# ADE9000.net
KiCad netlist of a schematic drawn in Altium Designer
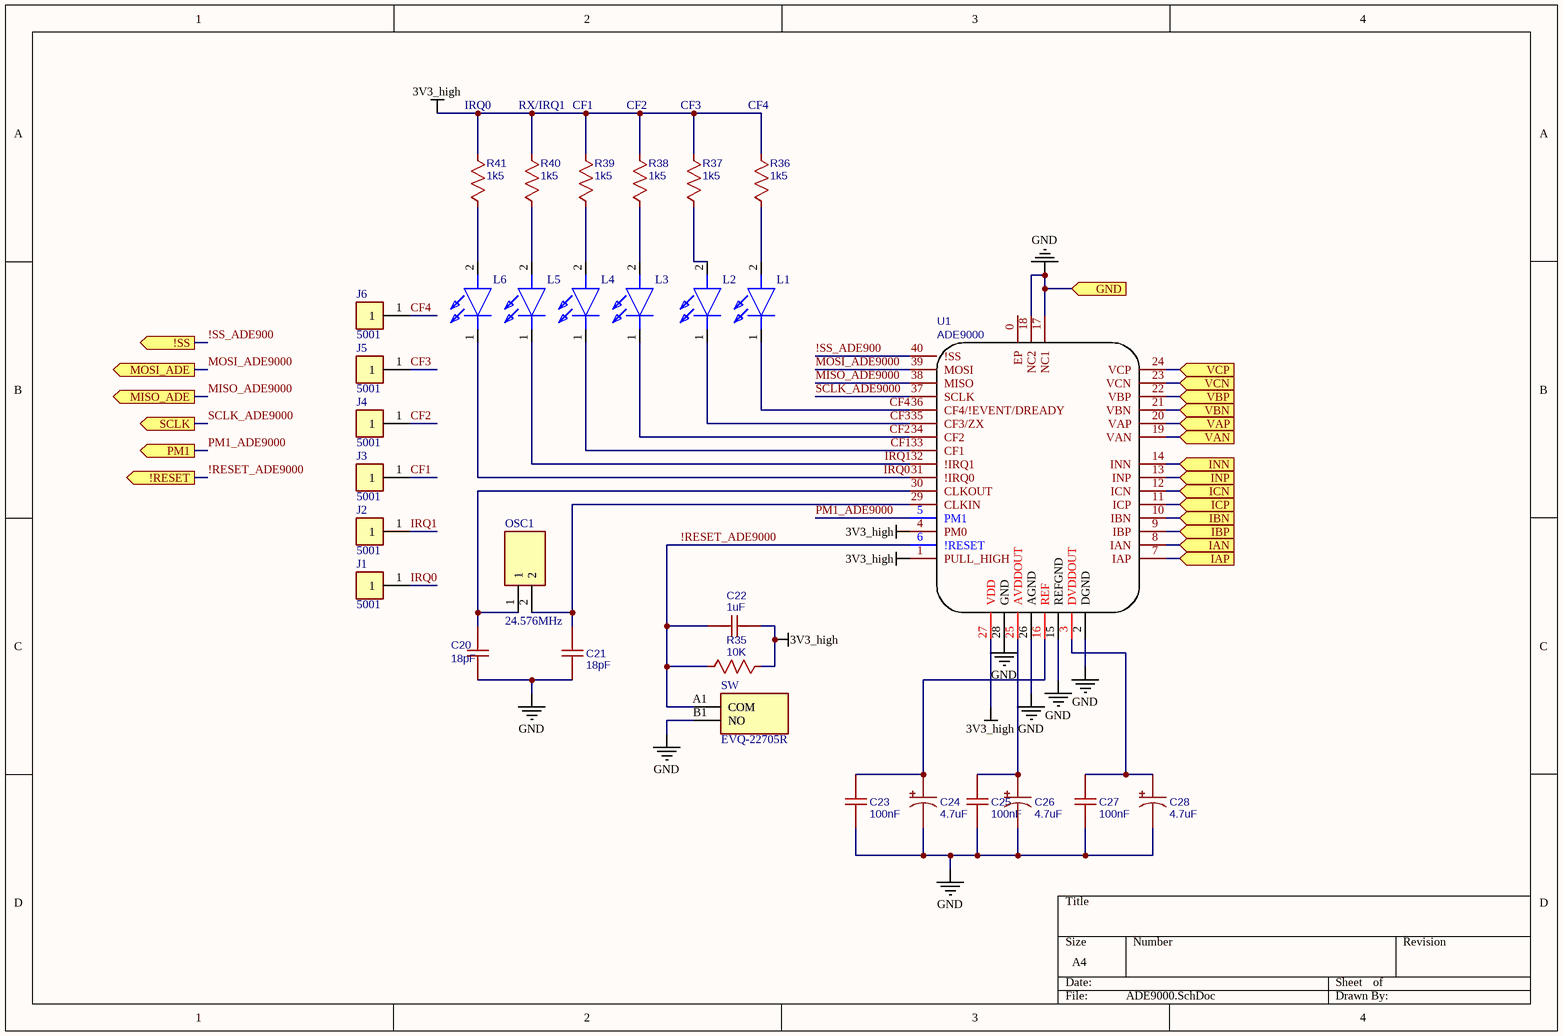
[diagram p0: ADE9000.SchDoc]

(export (version "E")
  (design (tool "Eeschema 10.0.6"))
  (components
    (comp (ref "C20")
      (value "18pF")
      (footprint "GRM31C5C1E104GA01L:CAPC3216X190")
      (libsource (lib "altium-import") (part "root_0_16pF_"))
    )
    (comp (ref "C21")
      (value "18pF")
      (footprint "GRM31C5C1E104GA01L:CAPC3216X190")
      (libsource (lib "altium-import") (part "root_0_16pF_"))
    )
    (comp (ref "C22")
      (value "1uF")
      (footprint "GRM31C5C1E104GA01L:CAPC3216X190")
      (libsource (lib "altium-import") (part "root_1_1uF_"))
    )
    (comp (ref "C23")
      (value "100nF")
      (footprint "GRM31C5C1E104GA01L:CAPC3216X190")
      (libsource (lib "altium-import") (part "root_0_100nF_"))
    )
    (comp (ref "C24")
      (value "4.7uF")
      (footprint "GRM31C5C1E104GA01L:CAPC3216X190")
      (libsource (lib "altium-import") (part "root_0_4.7uF_"))
    )
    (comp (ref "C25")
      (value "100nF")
      (footprint "GRM31C5C1E104GA01L:CAPC3216X190")
      (libsource (lib "altium-import") (part "root_0_100nF_"))
    )
    (comp (ref "C26")
      (value "4.7uF")
      (footprint "GRM31C5C1E104GA01L:CAPC3216X190")
      (libsource (lib "altium-import") (part "root_0_4.7uF_"))
    )
    (comp (ref "C27")
      (value "100nF")
      (footprint "GRM31C5C1E104GA01L:CAPC3216X190")
      (libsource (lib "altium-import") (part "root_0_100nF_"))
    )
    (comp (ref "C28")
      (value "4.7uF")
      (footprint "GRM31C5C1E104GA01L:CAPC3216X190")
      (libsource (lib "altium-import") (part "root_0_4.7uF_"))
    )
    (comp (ref "J1")
      (value "5001")
      (footprint "KEYSTONE_5001")
      (description "Conn Test Point SKT 1 POS ST Thru-Hole 1 Port")
      (fields (field (name "MF") "Keystone Electronics Corp."))
      (libsource (lib "5001") (part "5001"))
    )
    (comp (ref "J2")
      (value "5001")
      (footprint "KEYSTONE_5001")
      (description "Conn Test Point SKT 1 POS ST Thru-Hole 1 Port")
      (fields (field (name "MF") "Keystone Electronics Corp."))
      (libsource (lib "5001") (part "5001"))
    )
    (comp (ref "J3")
      (value "5001")
      (footprint "KEYSTONE_5001")
      (description "Conn Test Point SKT 1 POS ST Thru-Hole 1 Port")
      (fields (field (name "MF") "Keystone Electronics Corp."))
      (libsource (lib "5001") (part "5001"))
    )
    (comp (ref "J4")
      (value "5001")
      (footprint "KEYSTONE_5001")
      (description "Conn Test Point SKT 1 POS ST Thru-Hole 1 Port")
      (fields (field (name "MF") "Keystone Electronics Corp."))
      (libsource (lib "5001") (part "5001"))
    )
    (comp (ref "J5")
      (value "5001")
      (footprint "KEYSTONE_5001")
      (description "Conn Test Point SKT 1 POS ST Thru-Hole 1 Port")
      (fields (field (name "MF") "Keystone Electronics Corp."))
      (libsource (lib "5001") (part "5001"))
    )
    (comp (ref "J6")
      (value "5001")
      (footprint "KEYSTONE_5001")
      (description "Conn Test Point SKT 1 POS ST Thru-Hole 1 Port")
      (fields (field (name "MF") "Keystone Electronics Corp."))
      (libsource (lib "5001") (part "5001"))
    )
    (comp (ref "L1")
      (value "APT1608LZGCK")
      (footprint "SamacSys:LEDC1608X85N")
      (description "LED")
      (fields (field (name "MOUSER PART NUMBER") "604-APT1608LZGCK"))
      (libsource (lib "*") (part "APT1608LZGCK"))
    )
    (comp (ref "L2")
      (value "APT1608LZGCK")
      (footprint "SamacSys:LEDC1608X85N")
      (description "LED")
      (fields (field (name "MOUSER PART NUMBER") "604-APT1608LZGCK"))
      (libsource (lib "*") (part "APT1608LZGCK"))
    )
    (comp (ref "L3")
      (value "APT1608LZGCK")
      (footprint "SamacSys:LEDC1608X85N")
      (description "LED")
      (fields (field (name "MOUSER PART NUMBER") "604-APT1608LZGCK"))
      (libsource (lib "*") (part "APT1608LZGCK"))
    )
    (comp (ref "L4")
      (value "APT1608LZGCK")
      (footprint "SamacSys:LEDC1608X85N")
      (description "LED")
      (fields (field (name "MOUSER PART NUMBER") "604-APT1608LZGCK"))
      (libsource (lib "*") (part "APT1608LZGCK"))
    )
    (comp (ref "L5")
      (value "APT1608LZGCK")
      (footprint "SamacSys:LEDC1608X85N")
      (description "LED")
      (fields (field (name "MOUSER PART NUMBER") "604-APT1608LZGCK"))
      (libsource (lib "*") (part "APT1608LZGCK"))
    )
    (comp (ref "L6")
      (value "APT1608LZGCK")
      (footprint "SamacSys:LEDC1608X85N")
      (description "LED")
      (fields (field (name "MOUSER PART NUMBER") "604-APT1608LZGCK"))
      (libsource (lib "*") (part "APT1608LZGCK"))
    )
    (comp (ref "OSC1")
      (value "24.576MHz")
      (footprint "SamacSys:HC-49S_1")
      (description "Crystal or Oscillator")
      (fields (field (name "MANUFACTURER_PART_NUMBER") "9B16000381"))
      (libsource (lib "*") (part "9B16000381"))
    )
    (comp (ref "R35")
      (value "10K")
      (footprint "SamacSys:RESC3216X75N")
      (libsource (lib "altium-import") (part "root_0_10K_"))
    )
    (comp (ref "R36")
      (value "1k5")
      (footprint "SamacSys:RESC3216X75N")
      (libsource (lib "altium-import") (part "root_1_10K_"))
    )
    (comp (ref "R37")
      (value "1k5")
      (footprint "SamacSys:RESC3216X75N")
      (libsource (lib "altium-import") (part "root_1_10K_"))
    )
    (comp (ref "R38")
      (value "1k5")
      (footprint "SamacSys:RESC3216X75N")
      (libsource (lib "altium-import") (part "root_1_10K_"))
    )
    (comp (ref "R39")
      (value "1k5")
      (footprint "SamacSys:RESC3216X75N")
      (libsource (lib "altium-import") (part "root_1_10K_"))
    )
    (comp (ref "R40")
      (value "1k5")
      (footprint "SamacSys:RESC3216X75N")
      (libsource (lib "altium-import") (part "root_1_10K_"))
    )
    (comp (ref "R41")
      (value "1k5")
      (footprint "SamacSys:RESC3216X75N")
      (libsource (lib "altium-import") (part "root_1_10K_"))
    )
    (comp (ref "SW")
      (value "EVQ-22705R")
      (footprint "SamacSys:EVQ22705R")
      (description "Switch")
      (fields (field (name "MOUSER PART NUMBER") "667-EVQ-22705R"))
      (libsource (lib "*") (part "EVQ-22705R"))
    )
    (comp (ref "U1")
      (value "ADE9000")
      (footprint "SamacSys:QFN50P600X600X80-41N")
      (fields
        (field (name "BOM_MANUFACTURER PART") "ADE9000ACPZ-RL")
        (field (name "BOM_SUPPLIER PART") "ADE9000ACPZ-RLCT-ND")
      )
      (libsource (lib "altium-import") (part "root_2_ADE9000_"))
    )
  )
  (nets
    (net (code "1") (name "/!RESET_ADE9000") (class "Default")
      (node (ref "C22") (pin "2") (pinfunction "2_2") (pintype "passive"))
      (node (ref "R35") (pin "1") (pinfunction "1_1") (pintype "passive"))
      (node (ref "SW") (pin "A1") (pinfunction "COM_A1") (pintype "passive"))
      (node (ref "U1") (pin "6") (pinfunction "!RESET_6") (pintype "passive"))
    )
    (net (code "2") (name "/!SS_ADE900") (class "Default")
      (node (ref "U1") (pin "40") (pinfunction "!SS_40") (pintype "passive"))
    )
    (net (code "3") (name "/CF1") (class "Default")
      (node (ref "J3") (pin "1") (pinfunction "1_1") (pintype "passive"))
      (node (ref "L4") (pin "1") (pinfunction "K_1") (pintype "passive"))
      (node (ref "U1") (pin "33") (pinfunction "CF1_33") (pintype "passive"))
    )
    (net (code "4") (name "/CF2") (class "Default")
      (node (ref "J4") (pin "1") (pinfunction "1_1") (pintype "passive"))
      (node (ref "L3") (pin "1") (pinfunction "K_1") (pintype "passive"))
      (node (ref "U1") (pin "34") (pinfunction "CF2_34") (pintype "passive"))
    )
    (net (code "5") (name "/CF3") (class "Default")
      (node (ref "J5") (pin "1") (pinfunction "1_1") (pintype "passive"))
      (node (ref "L2") (pin "1") (pinfunction "K_1") (pintype "passive"))
      (node (ref "U1") (pin "35") (pinfunction "CF3/ZX_35") (pintype "passive"))
    )
    (net (code "6") (name "/CF4") (class "Default")
      (node (ref "J6") (pin "1") (pinfunction "1_1") (pintype "passive"))
      (node (ref "L1") (pin "1") (pinfunction "K_1") (pintype "passive"))
      (node (ref "U1") (pin "36") (pinfunction "CF4/!EVENT/DREADY_36") (pintype "passive"))
    )
    (net (code "7") (name "/IAN") (class "Default")
      (node (ref "U1") (pin "8") (pinfunction "IAN_8") (pintype "passive"))
    )
    (net (code "8") (name "/IAP") (class "Default")
      (node (ref "U1") (pin "7") (pinfunction "IAP_7") (pintype "passive"))
    )
    (net (code "9") (name "/IBN") (class "Default")
      (node (ref "U1") (pin "10") (pinfunction "IBN_10") (pintype "passive"))
    )
    (net (code "10") (name "/IBP") (class "Default")
      (node (ref "U1") (pin "9") (pinfunction "IBP_9") (pintype "passive"))
    )
    (net (code "11") (name "/ICN") (class "Default")
      (node (ref "U1") (pin "12") (pinfunction "ICN_12") (pintype "passive"))
    )
    (net (code "12") (name "/ICP") (class "Default")
      (node (ref "U1") (pin "11") (pinfunction "ICP_11") (pintype "passive"))
    )
    (net (code "13") (name "/INN") (class "Default")
      (node (ref "U1") (pin "14") (pinfunction "INN_14") (pintype "passive"))
    )
    (net (code "14") (name "/INP") (class "Default")
      (node (ref "U1") (pin "13") (pinfunction "INP_13") (pintype "passive"))
    )
    (net (code "15") (name "/IRQ0") (class "Default")
      (node (ref "J1") (pin "1") (pinfunction "1_1") (pintype "passive"))
      (node (ref "L6") (pin "1") (pinfunction "K_1") (pintype "passive"))
      (node (ref "U1") (pin "31") (pinfunction "!IRQ0_31") (pintype "passive"))
    )
    (net (code "16") (name "/IRQ1") (class "Default")
      (node (ref "J2") (pin "1") (pinfunction "1_1") (pintype "passive"))
      (node (ref "L5") (pin "1") (pinfunction "K_1") (pintype "passive"))
      (node (ref "U1") (pin "32") (pinfunction "!IRQ1_32") (pintype "passive"))
    )
    (net (code "17") (name "/MISO_ADE9000") (class "Default")
      (node (ref "U1") (pin "38") (pinfunction "MISO_38") (pintype "passive"))
    )
    (net (code "18") (name "/MOSI_ADE9000") (class "Default")
      (node (ref "U1") (pin "39") (pinfunction "MOSI_39") (pintype "passive"))
    )
    (net (code "19") (name "/PM1_ADE9000") (class "Default")
      (node (ref "U1") (pin "5") (pinfunction "PM1_5") (pintype "passive"))
    )
    (net (code "20") (name "/SCLK_ADE9000") (class "Default")
      (node (ref "U1") (pin "37") (pinfunction "SCLK_37") (pintype "passive"))
    )
    (net (code "21") (name "/VAN") (class "Default")
      (node (ref "U1") (pin "19") (pinfunction "VAN_19") (pintype "passive"))
    )
    (net (code "22") (name "/VAP") (class "Default")
      (node (ref "U1") (pin "20") (pinfunction "VAP_20") (pintype "passive"))
    )
    (net (code "23") (name "/VBN") (class "Default")
      (node (ref "U1") (pin "21") (pinfunction "VBN_21") (pintype "passive"))
    )
    (net (code "24") (name "/VBP") (class "Default")
      (node (ref "U1") (pin "22") (pinfunction "VBP_22") (pintype "passive"))
    )
    (net (code "25") (name "/VCN") (class "Default")
      (node (ref "U1") (pin "23") (pinfunction "VCN_23") (pintype "passive"))
    )
    (net (code "26") (name "/VCP") (class "Default")
      (node (ref "U1") (pin "24") (pinfunction "VCP_24") (pintype "passive"))
    )
    (net (code "27") (name "3V3_high") (class "Default")
      (node (ref "C22") (pin "1") (pinfunction "1_1") (pintype "passive"))
      (node (ref "R35") (pin "2") (pinfunction "2_2") (pintype "passive"))
      (node (ref "R36") (pin "2") (pinfunction "2_2") (pintype "passive"))
      (node (ref "R37") (pin "2") (pinfunction "2_2") (pintype "passive"))
      (node (ref "R38") (pin "2") (pinfunction "2_2") (pintype "passive"))
      (node (ref "R39") (pin "2") (pinfunction "2_2") (pintype "passive"))
      (node (ref "R40") (pin "2") (pinfunction "2_2") (pintype "passive"))
      (node (ref "R41") (pin "2") (pinfunction "2_2") (pintype "passive"))
      (node (ref "U1") (pin "1") (pinfunction "PULL_HIGH_1") (pintype "passive"))
      (node (ref "U1") (pin "27") (pinfunction "VDD_27") (pintype "passive"))
      (node (ref "U1") (pin "4") (pinfunction "PM0_4") (pintype "passive"))
    )
    (net (code "28") (name "GND") (class "Default")
      (node (ref "C20") (pin "1") (pinfunction "1_1") (pintype "passive"))
      (node (ref "C21") (pin "1") (pinfunction "1_1") (pintype "passive"))
      (node (ref "C23") (pin "1") (pinfunction "1_1") (pintype "passive"))
      (node (ref "C24") (pin "2") (pinfunction "2_2") (pintype "passive"))
      (node (ref "C25") (pin "1") (pinfunction "1_1") (pintype "passive"))
      (node (ref "C26") (pin "2") (pinfunction "2_2") (pintype "passive"))
      (node (ref "C27") (pin "1") (pinfunction "1_1") (pintype "passive"))
      (node (ref "C28") (pin "2") (pinfunction "2_2") (pintype "passive"))
      (node (ref "SW") (pin "B1") (pinfunction "NO_B1") (pintype "passive"))
      (node (ref "U1") (pin "15") (pinfunction "REFGND_15") (pintype "passive"))
      (node (ref "U1") (pin "17") (pinfunction "NC1_17") (pintype "passive"))
      (node (ref "U1") (pin "18") (pinfunction "NC2_18") (pintype "passive"))
      (node (ref "U1") (pin "2") (pinfunction "DGND_2") (pintype "passive"))
      (node (ref "U1") (pin "26") (pinfunction "AGND_26") (pintype "passive"))
      (node (ref "U1") (pin "28") (pinfunction "GND_28") (pintype "passive"))
    )
    (net (code "29") (name "Net-(L1-A)") (class "Default")
      (node (ref "L1") (pin "2") (pinfunction "A_2") (pintype "passive"))
      (node (ref "R36") (pin "1") (pinfunction "1_1") (pintype "passive"))
    )
    (net (code "30") (name "Net-(L2-A)") (class "Default")
      (node (ref "L2") (pin "2") (pinfunction "A_2") (pintype "passive"))
      (node (ref "R37") (pin "1") (pinfunction "1_1") (pintype "passive"))
    )
    (net (code "31") (name "Net-(L3-A)") (class "Default")
      (node (ref "L3") (pin "2") (pinfunction "A_2") (pintype "passive"))
      (node (ref "R38") (pin "1") (pinfunction "1_1") (pintype "passive"))
    )
    (net (code "32") (name "Net-(L4-A)") (class "Default")
      (node (ref "L4") (pin "2") (pinfunction "A_2") (pintype "passive"))
      (node (ref "R39") (pin "1") (pinfunction "1_1") (pintype "passive"))
    )
    (net (code "33") (name "Net-(L5-A)") (class "Default")
      (node (ref "L5") (pin "2") (pinfunction "A_2") (pintype "passive"))
      (node (ref "R40") (pin "1") (pinfunction "1_1") (pintype "passive"))
    )
    (net (code "34") (name "Net-(L6-A)") (class "Default")
      (node (ref "L6") (pin "2") (pinfunction "A_2") (pintype "passive"))
      (node (ref "R41") (pin "1") (pinfunction "1_1") (pintype "passive"))
    )
    (net (code "35") (name "Net-(U1-AVDDOUT)") (class "Default")
      (node (ref "C25") (pin "2") (pinfunction "2_2") (pintype "passive"))
      (node (ref "C26") (pin "1") (pinfunction "1_1") (pintype "passive"))
      (node (ref "U1") (pin "25") (pinfunction "AVDDOUT_25") (pintype "passive"))
    )
    (net (code "36") (name "Net-(U1-CLKIN)") (class "Default")
      (node (ref "C21") (pin "2") (pinfunction "2_2") (pintype "passive"))
      (node (ref "OSC1") (pin "2") (pinfunction "2_2") (pintype "passive"))
      (node (ref "U1") (pin "29") (pinfunction "CLKIN_29") (pintype "passive"))
    )
    (net (code "37") (name "Net-(U1-CLKOUT)") (class "Default")
      (node (ref "C20") (pin "2") (pinfunction "2_2") (pintype "passive"))
      (node (ref "OSC1") (pin "1") (pinfunction "1_1") (pintype "passive"))
      (node (ref "U1") (pin "30") (pinfunction "CLKOUT_30") (pintype "passive"))
    )
    (net (code "38") (name "Net-(U1-DVDDOUT)") (class "Default")
      (node (ref "C27") (pin "2") (pinfunction "2_2") (pintype "passive"))
      (node (ref "C28") (pin "1") (pinfunction "1_1") (pintype "passive"))
      (node (ref "U1") (pin "3") (pinfunction "DVDDOUT_3") (pintype "passive"))
    )
    (net (code "39") (name "Net-(U1-REF)") (class "Default")
      (node (ref "C23") (pin "2") (pinfunction "2_2") (pintype "passive"))
      (node (ref "C24") (pin "1") (pinfunction "1_1") (pintype "passive"))
      (node (ref "U1") (pin "16") (pinfunction "REF_16") (pintype "passive"))
    )
    (net (code "40") (name "unconnected-(U1-EP-Pad0)") (class "Default")
      (node (ref "U1") (pin "0") (pinfunction "EP_0") (pintype "passive"))
    )
  )
)
